# SD-eMMC.net
KiCad netlist of a schematic drawn in Altium Designer
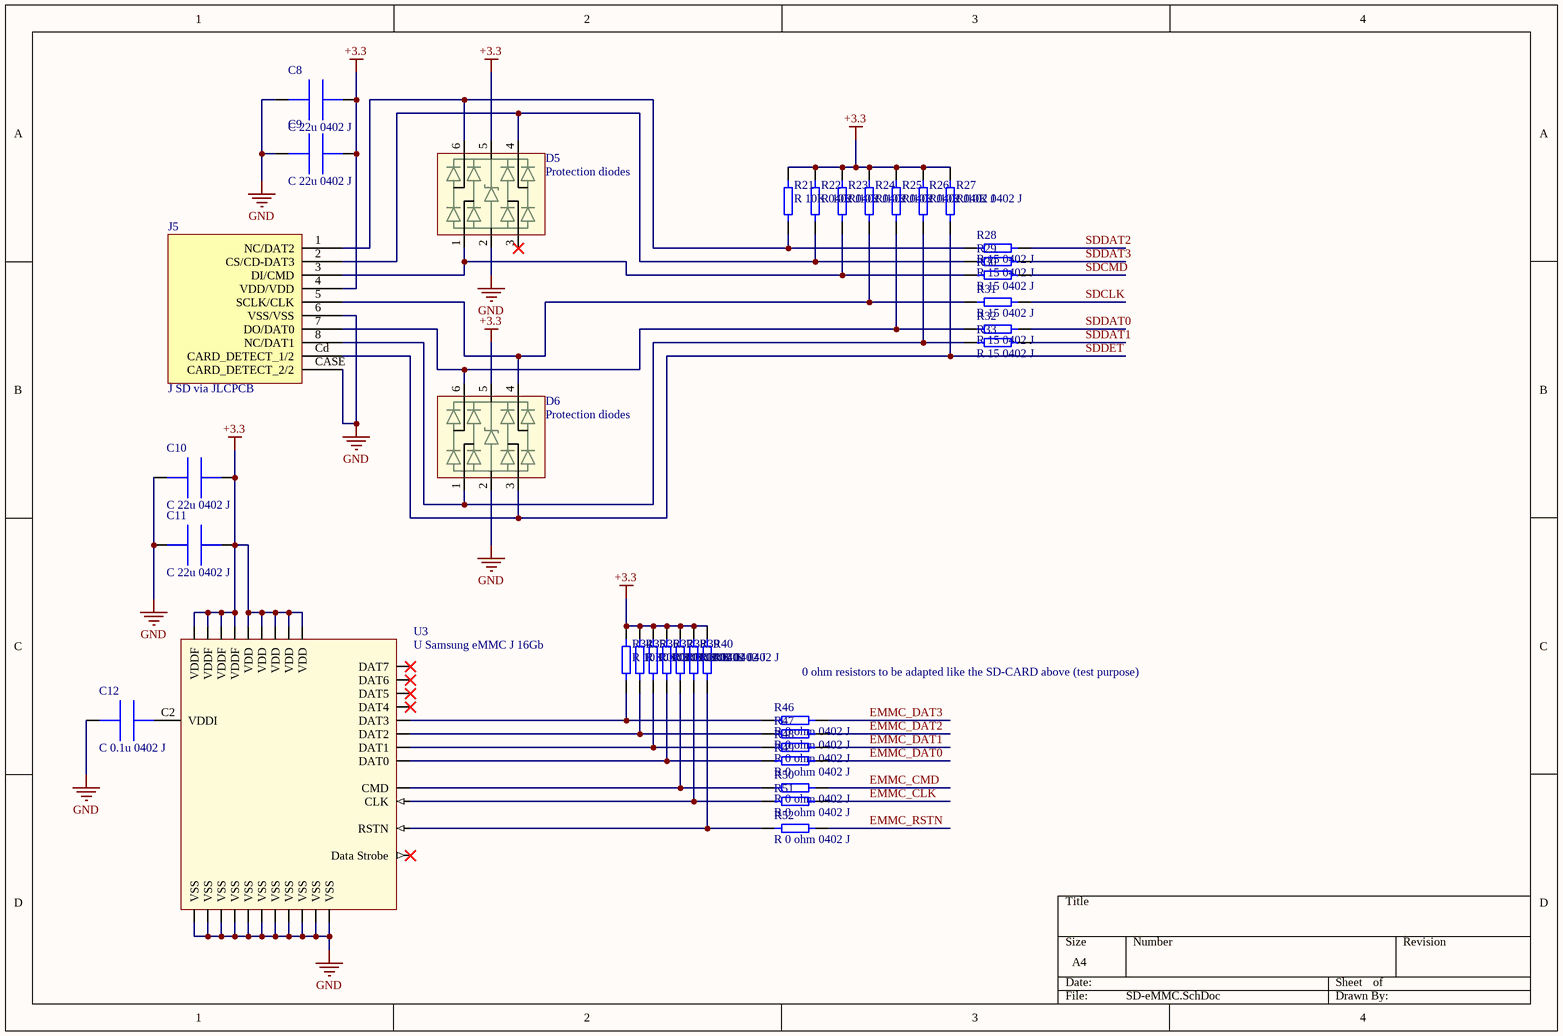
[diagram p0: SD-eMMC.SchDoc]

(export (version "E")
  (design (tool "Eeschema 10.0.6"))
  (components
    (comp (ref "C8")
      (value "C 22u 0402 J")
      (footprint "C0402")
      (description "Multi-Layer Ceramic Capacitor 22uF 2.5VDC X6S 20% 0402 Paper T/R GRM155C80E226ME11D")
      (fields
        (field (name "MANUFACTURER") "Murata")
        (field (name "MANUFACTURER PART NUMBER") "GRM155C80E226ME11D")
      )
      (libsource (lib "Schlib1") (part "C 22u 0402 J"))
    )
    (comp (ref "C9")
      (value "C 22u 0402 J")
      (footprint "C0402")
      (description "Multi-Layer Ceramic Capacitor 22uF 2.5VDC X6S 20% 0402 Paper T/R GRM155C80E226ME11D")
      (fields
        (field (name "MANUFACTURER") "Murata")
        (field (name "MANUFACTURER PART NUMBER") "GRM155C80E226ME11D")
      )
      (libsource (lib "Schlib1") (part "C 22u 0402 J"))
    )
    (comp (ref "C10")
      (value "C 22u 0402 J")
      (footprint "C0402")
      (description "Multi-Layer Ceramic Capacitor 22uF 2.5VDC X6S 20% 0402 Paper T/R GRM155C80E226ME11D")
      (fields
        (field (name "MANUFACTURER") "Murata")
        (field (name "MANUFACTURER PART NUMBER") "GRM155C80E226ME11D")
      )
      (libsource (lib "Schlib1") (part "C 22u 0402 J"))
    )
    (comp (ref "C11")
      (value "C 22u 0402 J")
      (footprint "C0402")
      (description "Multi-Layer Ceramic Capacitor 22uF 2.5VDC X6S 20% 0402 Paper T/R GRM155C80E226ME11D")
      (fields
        (field (name "MANUFACTURER") "Murata")
        (field (name "MANUFACTURER PART NUMBER") "GRM155C80E226ME11D")
      )
      (libsource (lib "Schlib1") (part "C 22u 0402 J"))
    )
    (comp (ref "C12")
      (value "C 0.1u 0402 J")
      (footprint "C0402")
      (description "Cap Ceramic 0.1uF 50V X7R 10% Pad SMD 0402 125C Low ESR Automotive CL05B104KB54PNC")
      (fields
        (field (name "MANUFACTURER") "Samsung")
        (field (name "MANUFACTURER PART NUMBER") "CL05B104KB54PNC")
      )
      (libsource (lib "Schlib1") (part "C 0.1u 0402 J"))
    )
    (comp (ref "D5")
      (value "Protection diodes")
      (footprint "SOT23-SRV05")
      (description "SEMTECH - SRV05-4.TCT - ESD Protection Device, TVS, 17.5 V, SOT-23, 6 Pins, 5 V, 300 W")
      (fields (field (name "MANUFACTURER") "Semtech") (field (name "MANUFACTURER PART NUMBER") "SRV05-4.TCT"))
      (libsource (lib "Schlib1") (part "D SRV05-4.TCT"))
    )
    (comp (ref "D6")
      (value "Protection diodes")
      (footprint "SOT23-SRV05")
      (description "SEMTECH - SRV05-4.TCT - ESD Protection Device, TVS, 17.5 V, SOT-23, 6 Pins, 5 V, 300 W")
      (fields (field (name "MANUFACTURER") "Semtech") (field (name "MANUFACTURER PART NUMBER") "SRV05-4.TCT"))
      (libsource (lib "Schlib1") (part "D SRV05-4.TCT"))
    )
    (comp (ref "J5")
      (value "J SD via JLCPCB")
      (footprint "SOFNG TF-15X15 SD JLCPCB")
      (description "Deck MicroSD card (TF card) Self bomb SMD SD Card Connectors ROHS")
      (fields (field (name "MANUFACTURER") "SOFNG") (field (name "MANUFACTURER PART NUMBER") "TF-15x15"))
      (libsource (lib "Schlib1") (part "J SD via JLCPCB"))
    )
    (comp (ref "R21")
      (value "R 10K 0402 J")
      (footprint "R0402")
      (description "Res Thick Film 0402 10K Ohm 1% 0.063W(1/16W) ±100ppm/C Pad SMD Automotive T/R AC0402FR-0710KL")
      (fields
        (field (name "MANUFACTURER") "Yageo")
        (field (name "MANUFACTURER PART NUMBER") "AC0402FR-0710KL")
      )
      (libsource (lib "Schlib1") (part "R 10K 0402 J"))
    )
    (comp (ref "R22")
      (value "R 10K 0402 J")
      (footprint "R0402")
      (description "Res Thick Film 0402 10K Ohm 1% 0.063W(1/16W) ±100ppm/C Pad SMD Automotive T/R AC0402FR-0710KL")
      (fields
        (field (name "MANUFACTURER") "Yageo")
        (field (name "MANUFACTURER PART NUMBER") "AC0402FR-0710KL")
      )
      (libsource (lib "Schlib1") (part "R 10K 0402 J"))
    )
    (comp (ref "R23")
      (value "R 10K 0402 J")
      (footprint "R0402")
      (description "Res Thick Film 0402 10K Ohm 1% 0.063W(1/16W) ±100ppm/C Pad SMD Automotive T/R AC0402FR-0710KL")
      (fields
        (field (name "MANUFACTURER") "Yageo")
        (field (name "MANUFACTURER PART NUMBER") "AC0402FR-0710KL")
      )
      (libsource (lib "Schlib1") (part "R 10K 0402 J"))
    )
    (comp (ref "R24")
      (value "R 10K 0402 J")
      (footprint "R0402")
      (description "Res Thick Film 0402 10K Ohm 1% 0.063W(1/16W) ±100ppm/C Pad SMD Automotive T/R AC0402FR-0710KL")
      (fields
        (field (name "MANUFACTURER") "Yageo")
        (field (name "MANUFACTURER PART NUMBER") "AC0402FR-0710KL")
      )
      (libsource (lib "Schlib1") (part "R 10K 0402 J"))
    )
    (comp (ref "R25")
      (value "R 10K 0402 J")
      (footprint "R0402")
      (description "Res Thick Film 0402 10K Ohm 1% 0.063W(1/16W) ±100ppm/C Pad SMD Automotive T/R AC0402FR-0710KL")
      (fields
        (field (name "MANUFACTURER") "Yageo")
        (field (name "MANUFACTURER PART NUMBER") "AC0402FR-0710KL")
      )
      (libsource (lib "Schlib1") (part "R 10K 0402 J"))
    )
    (comp (ref "R26")
      (value "R 10K 0402 J")
      (footprint "R0402")
      (description "Res Thick Film 0402 10K Ohm 1% 0.063W(1/16W) ±100ppm/C Pad SMD Automotive T/R AC0402FR-0710KL")
      (fields
        (field (name "MANUFACTURER") "Yageo")
        (field (name "MANUFACTURER PART NUMBER") "AC0402FR-0710KL")
      )
      (libsource (lib "Schlib1") (part "R 10K 0402 J"))
    )
    (comp (ref "R27")
      (value "R 10K 0402 J")
      (footprint "R0402")
      (description "Res Thick Film 0402 10K Ohm 1% 0.063W(1/16W) ±100ppm/C Pad SMD Automotive T/R AC0402FR-0710KL")
      (fields
        (field (name "MANUFACTURER") "Yageo")
        (field (name "MANUFACTURER PART NUMBER") "AC0402FR-0710KL")
      )
      (libsource (lib "Schlib1") (part "R 10K 0402 J"))
    )
    (comp (ref "R28")
      (value "R 15 0402 J")
      (footprint "R0402")
      (description "Res Thick Film 0402 15 Ohm 5% 1/10W ±200ppm/°C Molded SMD Punched Carrier T/R ERJ-2GEJ150X")
      (fields
        (field (name "MANUFACTURER") "Panasonic")
        (field (name "MANUFACTURER PART NUMBER") "ERJ-2GEJ150X")
      )
      (libsource (lib "Schlib1") (part "R 15 0402 J"))
    )
    (comp (ref "R29")
      (value "R 15 0402 J")
      (footprint "R0402")
      (description "Res Thick Film 0402 15 Ohm 5% 1/10W ±200ppm/°C Molded SMD Punched Carrier T/R ERJ-2GEJ150X")
      (fields
        (field (name "MANUFACTURER") "Panasonic")
        (field (name "MANUFACTURER PART NUMBER") "ERJ-2GEJ150X")
      )
      (libsource (lib "Schlib1") (part "R 15 0402 J"))
    )
    (comp (ref "R30")
      (value "R 15 0402 J")
      (footprint "R0402")
      (description "Res Thick Film 0402 15 Ohm 5% 1/10W ±200ppm/°C Molded SMD Punched Carrier T/R ERJ-2GEJ150X")
      (fields
        (field (name "MANUFACTURER") "Panasonic")
        (field (name "MANUFACTURER PART NUMBER") "ERJ-2GEJ150X")
      )
      (libsource (lib "Schlib1") (part "R 15 0402 J"))
    )
    (comp (ref "R31")
      (value "R 15 0402 J")
      (footprint "R0402")
      (description "Res Thick Film 0402 15 Ohm 5% 1/10W ±200ppm/°C Molded SMD Punched Carrier T/R ERJ-2GEJ150X")
      (fields
        (field (name "MANUFACTURER") "Panasonic")
        (field (name "MANUFACTURER PART NUMBER") "ERJ-2GEJ150X")
      )
      (libsource (lib "Schlib1") (part "R 15 0402 J"))
    )
    (comp (ref "R32")
      (value "R 15 0402 J")
      (footprint "R0402")
      (description "Res Thick Film 0402 15 Ohm 5% 1/10W ±200ppm/°C Molded SMD Punched Carrier T/R ERJ-2GEJ150X")
      (fields
        (field (name "MANUFACTURER") "Panasonic")
        (field (name "MANUFACTURER PART NUMBER") "ERJ-2GEJ150X")
      )
      (libsource (lib "Schlib1") (part "R 15 0402 J"))
    )
    (comp (ref "R33")
      (value "R 15 0402 J")
      (footprint "R0402")
      (description "Res Thick Film 0402 15 Ohm 5% 1/10W ±200ppm/°C Molded SMD Punched Carrier T/R ERJ-2GEJ150X")
      (fields
        (field (name "MANUFACTURER") "Panasonic")
        (field (name "MANUFACTURER PART NUMBER") "ERJ-2GEJ150X")
      )
      (libsource (lib "Schlib1") (part "R 15 0402 J"))
    )
    (comp (ref "R34")
      (value "R 10K 0402 J")
      (footprint "R0402")
      (description "Res Thick Film 0402 10K Ohm 1% 0.063W(1/16W) ±100ppm/C Pad SMD Automotive T/R AC0402FR-0710KL")
      (fields
        (field (name "MANUFACTURER") "Yageo")
        (field (name "MANUFACTURER PART NUMBER") "AC0402FR-0710KL")
      )
      (libsource (lib "Schlib1") (part "R 10K 0402 J"))
    )
    (comp (ref "R35")
      (value "R 10K 0402 J")
      (footprint "R0402")
      (description "Res Thick Film 0402 10K Ohm 1% 0.063W(1/16W) ±100ppm/C Pad SMD Automotive T/R AC0402FR-0710KL")
      (fields
        (field (name "MANUFACTURER") "Yageo")
        (field (name "MANUFACTURER PART NUMBER") "AC0402FR-0710KL")
      )
      (libsource (lib "Schlib1") (part "R 10K 0402 J"))
    )
    (comp (ref "R36")
      (value "R 10K 0402 J")
      (footprint "R0402")
      (description "Res Thick Film 0402 10K Ohm 1% 0.063W(1/16W) ±100ppm/C Pad SMD Automotive T/R AC0402FR-0710KL")
      (fields
        (field (name "MANUFACTURER") "Yageo")
        (field (name "MANUFACTURER PART NUMBER") "AC0402FR-0710KL")
      )
      (libsource (lib "Schlib1") (part "R 10K 0402 J"))
    )
    (comp (ref "R37")
      (value "R 10K 0402 J")
      (footprint "R0402")
      (description "Res Thick Film 0402 10K Ohm 1% 0.063W(1/16W) ±100ppm/C Pad SMD Automotive T/R AC0402FR-0710KL")
      (fields
        (field (name "MANUFACTURER") "Yageo")
        (field (name "MANUFACTURER PART NUMBER") "AC0402FR-0710KL")
      )
      (libsource (lib "Schlib1") (part "R 10K 0402 J"))
    )
    (comp (ref "R38")
      (value "R 10K 0402 J")
      (footprint "R0402")
      (description "Res Thick Film 0402 10K Ohm 1% 0.063W(1/16W) ±100ppm/C Pad SMD Automotive T/R AC0402FR-0710KL")
      (fields
        (field (name "MANUFACTURER") "Yageo")
        (field (name "MANUFACTURER PART NUMBER") "AC0402FR-0710KL")
      )
      (libsource (lib "Schlib1") (part "R 10K 0402 J"))
    )
    (comp (ref "R39")
      (value "R 10K 0402 J")
      (footprint "R0402")
      (description "Res Thick Film 0402 10K Ohm 1% 0.063W(1/16W) ±100ppm/C Pad SMD Automotive T/R AC0402FR-0710KL")
      (fields
        (field (name "MANUFACTURER") "Yageo")
        (field (name "MANUFACTURER PART NUMBER") "AC0402FR-0710KL")
      )
      (libsource (lib "Schlib1") (part "R 10K 0402 J"))
    )
    (comp (ref "R40")
      (value "R 10K 0402 J")
      (footprint "R0402")
      (description "Res Thick Film 0402 10K Ohm 1% 0.063W(1/16W) ±100ppm/C Pad SMD Automotive T/R AC0402FR-0710KL")
      (fields
        (field (name "MANUFACTURER") "Yageo")
        (field (name "MANUFACTURER PART NUMBER") "AC0402FR-0710KL")
      )
      (libsource (lib "Schlib1") (part "R 10K 0402 J"))
    )
    (comp (ref "R46")
      (value "R 0 ohm 0402 J")
      (footprint "R0402")
      (description "RC Series 0402 0.063 W 0 Ohm Jumper Surface Mount Thick Film Chip Resistor RC0402FR-070RL")
      (fields
        (field (name "MANUFACTURER") "Yageo")
        (field (name "MANUFACTURER PART NUMBER") "RC0402FR-070RL")
      )
      (libsource (lib "Schlib1") (part "R 0 ohm 0402 J"))
    )
    (comp (ref "R47")
      (value "R 0 ohm 0402 J")
      (footprint "R0402")
      (description "RC Series 0402 0.063 W 0 Ohm Jumper Surface Mount Thick Film Chip Resistor RC0402FR-070RL")
      (fields
        (field (name "MANUFACTURER") "Yageo")
        (field (name "MANUFACTURER PART NUMBER") "RC0402FR-070RL")
      )
      (libsource (lib "Schlib1") (part "R 0 ohm 0402 J"))
    )
    (comp (ref "R48")
      (value "R 0 ohm 0402 J")
      (footprint "R0402")
      (description "RC Series 0402 0.063 W 0 Ohm Jumper Surface Mount Thick Film Chip Resistor RC0402FR-070RL")
      (fields
        (field (name "MANUFACTURER") "Yageo")
        (field (name "MANUFACTURER PART NUMBER") "RC0402FR-070RL")
      )
      (libsource (lib "Schlib1") (part "R 0 ohm 0402 J"))
    )
    (comp (ref "R49")
      (value "R 0 ohm 0402 J")
      (footprint "R0402")
      (description "RC Series 0402 0.063 W 0 Ohm Jumper Surface Mount Thick Film Chip Resistor RC0402FR-070RL")
      (fields
        (field (name "MANUFACTURER") "Yageo")
        (field (name "MANUFACTURER PART NUMBER") "RC0402FR-070RL")
      )
      (libsource (lib "Schlib1") (part "R 0 ohm 0402 J"))
    )
    (comp (ref "R50")
      (value "R 0 ohm 0402 J")
      (footprint "R0402")
      (description "RC Series 0402 0.063 W 0 Ohm Jumper Surface Mount Thick Film Chip Resistor RC0402FR-070RL")
      (fields
        (field (name "MANUFACTURER") "Yageo")
        (field (name "MANUFACTURER PART NUMBER") "RC0402FR-070RL")
      )
      (libsource (lib "Schlib1") (part "R 0 ohm 0402 J"))
    )
    (comp (ref "R51")
      (value "R 0 ohm 0402 J")
      (footprint "R0402")
      (description "RC Series 0402 0.063 W 0 Ohm Jumper Surface Mount Thick Film Chip Resistor RC0402FR-070RL")
      (fields
        (field (name "MANUFACTURER") "Yageo")
        (field (name "MANUFACTURER PART NUMBER") "RC0402FR-070RL")
      )
      (libsource (lib "Schlib1") (part "R 0 ohm 0402 J"))
    )
    (comp (ref "R52")
      (value "R 0 ohm 0402 J")
      (footprint "R0402")
      (description "RC Series 0402 0.063 W 0 Ohm Jumper Surface Mount Thick Film Chip Resistor RC0402FR-070RL")
      (fields
        (field (name "MANUFACTURER") "Yageo")
        (field (name "MANUFACTURER PART NUMBER") "RC0402FR-070RL")
      )
      (libsource (lib "Schlib1") (part "R 0 ohm 0402 J"))
    )
    (comp (ref "U3")
      (value "U Samsung eMMC J 16Gb")
      (footprint "BGA153C50P14X14_1150X1300X92")
      (description "KLMAG1JETD-B041 16Gbit -25℃~+85℃ 2.7V~3.6V eMMC 5.1 FBGA-153 eMMC ROHS")
      (fields
        (field (name "MANUFACTURER") "Samsung")
        (field (name "MANUFACTURER PART NUMBER") "KLMAG1JETD-B041")
      )
      (libsource (lib "Schlib1") (part "U Samsung eMMC J 16Gb"))
    )
  )
  (nets
    (net (code "1") (name "+3.3") (class "Default")
      (node (ref "C10") (pin "2") (pinfunction "2_2") (pintype "passive"))
      (node (ref "C11") (pin "2") (pinfunction "2_2") (pintype "passive"))
      (node (ref "C8") (pin "2") (pinfunction "2_2") (pintype "passive"))
      (node (ref "C9") (pin "2") (pinfunction "2_2") (pintype "passive"))
      (node (ref "D5") (pin "5") (pinfunction "5_5") (pintype "passive"))
      (node (ref "D6") (pin "5") (pinfunction "5_5") (pintype "passive"))
      (node (ref "J5") (pin "4") (pinfunction "VDD/VDD_4") (pintype "passive"))
      (node (ref "R21") (pin "2") (pinfunction "2_2") (pintype "passive"))
      (node (ref "R22") (pin "2") (pinfunction "2_2") (pintype "passive"))
      (node (ref "R23") (pin "2") (pinfunction "2_2") (pintype "passive"))
      (node (ref "R24") (pin "2") (pinfunction "2_2") (pintype "passive"))
      (node (ref "R25") (pin "2") (pinfunction "2_2") (pintype "passive"))
      (node (ref "R26") (pin "2") (pinfunction "2_2") (pintype "passive"))
      (node (ref "R27") (pin "2") (pinfunction "2_2") (pintype "passive"))
      (node (ref "R34") (pin "2") (pinfunction "2_2") (pintype "passive"))
      (node (ref "R35") (pin "2") (pinfunction "2_2") (pintype "passive"))
      (node (ref "R36") (pin "2") (pinfunction "2_2") (pintype "passive"))
      (node (ref "R37") (pin "2") (pinfunction "2_2") (pintype "passive"))
      (node (ref "R38") (pin "1") (pinfunction "1_1") (pintype "passive"))
      (node (ref "R39") (pin "2") (pinfunction "2_2") (pintype "passive"))
      (node (ref "R40") (pin "1") (pinfunction "1_1") (pintype "passive"))
      (node (ref "U3") (pin "C6") (pinfunction "VDD_C6") (pintype "power_in"))
      (node (ref "U3") (pin "E6") (pinfunction "VDDF_E6") (pintype "power_in"))
      (node (ref "U3") (pin "F5") (pinfunction "VDDF_F5") (pintype "power_in"))
      (node (ref "U3") (pin "J10") (pinfunction "VDDF_J10") (pintype "power_in"))
      (node (ref "U3") (pin "K9") (pinfunction "VDDF_K9") (pintype "power_in"))
      (node (ref "U3") (pin "M4") (pinfunction "VDD_M4") (pintype "power_in"))
      (node (ref "U3") (pin "N4") (pinfunction "VDD_N4") (pintype "power_in"))
      (node (ref "U3") (pin "P3") (pinfunction "VDD_P3") (pintype "power_in"))
      (node (ref "U3") (pin "P5") (pinfunction "VDD_P5") (pintype "power_in"))
    )
    (net (code "2") (name "/EMMC_CLK") (class "Default")
      (node (ref "R51") (pin "2") (pinfunction "2_2") (pintype "passive"))
    )
    (net (code "3") (name "/EMMC_CMD") (class "Default")
      (node (ref "R50") (pin "2") (pinfunction "2_2") (pintype "passive"))
    )
    (net (code "4") (name "/EMMC_DAT0") (class "Default")
      (node (ref "R49") (pin "2") (pinfunction "2_2") (pintype "passive"))
    )
    (net (code "5") (name "/EMMC_DAT1") (class "Default")
      (node (ref "R48") (pin "2") (pinfunction "2_2") (pintype "passive"))
    )
    (net (code "6") (name "/EMMC_DAT2") (class "Default")
      (node (ref "R47") (pin "2") (pinfunction "2_2") (pintype "passive"))
    )
    (net (code "7") (name "/EMMC_DAT3") (class "Default")
      (node (ref "R46") (pin "2") (pinfunction "2_2") (pintype "passive"))
    )
    (net (code "8") (name "/EMMC_RSTN") (class "Default")
      (node (ref "R52") (pin "2") (pinfunction "2_2") (pintype "passive"))
    )
    (net (code "9") (name "/SDCLK") (class "Default")
      (node (ref "R31") (pin "2") (pinfunction "2_2") (pintype "passive"))
    )
    (net (code "10") (name "/SDCMD") (class "Default")
      (node (ref "R30") (pin "2") (pinfunction "2_2") (pintype "passive"))
    )
    (net (code "11") (name "/SDDAT0") (class "Default")
      (node (ref "R32") (pin "2") (pinfunction "2_2") (pintype "passive"))
    )
    (net (code "12") (name "/SDDAT1") (class "Default")
      (node (ref "R33") (pin "2") (pinfunction "2_2") (pintype "passive"))
    )
    (net (code "13") (name "/SDDAT2") (class "Default")
      (node (ref "R28") (pin "2") (pinfunction "2_2") (pintype "passive"))
    )
    (net (code "14") (name "/SDDAT3") (class "Default")
      (node (ref "R29") (pin "2") (pinfunction "2_2") (pintype "passive"))
    )
    (net (code "15") (name "/SDDET") (class "Default")
      (node (ref "D6") (pin "3") (pinfunction "3_3") (pintype "passive"))
      (node (ref "J5") (pin "Cd") (pinfunction "CARD_DETECT_1/2_Cd") (pintype "passive"))
      (node (ref "R27") (pin "1") (pinfunction "1_1") (pintype "passive"))
    )
    (net (code "16") (name "GND") (class "Default")
      (node (ref "C10") (pin "1") (pinfunction "1_1") (pintype "passive"))
      (node (ref "C11") (pin "1") (pinfunction "1_1") (pintype "passive"))
      (node (ref "C12") (pin "1") (pinfunction "1_1") (pintype "passive"))
      (node (ref "C8") (pin "1") (pinfunction "1_1") (pintype "passive"))
      (node (ref "C9") (pin "1") (pinfunction "1_1") (pintype "passive"))
      (node (ref "D5") (pin "2") (pinfunction "2_2") (pintype "passive"))
      (node (ref "D6") (pin "2") (pinfunction "2_2") (pintype "passive"))
      (node (ref "J5") (pin "6") (pinfunction "VSS/VSS_6") (pintype "passive"))
      (node (ref "J5") (pin "CASE") (pinfunction "CARD_DETECT_2/2_CASE") (pintype "passive"))
      (node (ref "U3") (pin "A6") (pinfunction "VSS_A6") (pintype "power_in"))
      (node (ref "U3") (pin "C4") (pinfunction "VSS_C4") (pintype "power_in"))
      (node (ref "U3") (pin "E7") (pinfunction "VSS_E7") (pintype "power_in"))
      (node (ref "U3") (pin "G5") (pinfunction "VSS_G5") (pintype "power_in"))
      (node (ref "U3") (pin "H10") (pinfunction "VSS_H10") (pintype "power_in"))
      (node (ref "U3") (pin "J5") (pinfunction "VSS_J5") (pintype "power_in"))
      (node (ref "U3") (pin "K8") (pinfunction "VSS_K8") (pintype "power_in"))
      (node (ref "U3") (pin "N2") (pinfunction "VSS_N2") (pintype "power_in"))
      (node (ref "U3") (pin "N5") (pinfunction "VSS_N5") (pintype "power_in"))
      (node (ref "U3") (pin "P4") (pinfunction "VSS_P4") (pintype "power_in"))
      (node (ref "U3") (pin "P6") (pinfunction "VSS_P6") (pintype "power_in"))
    )
    (net (code "17") (name "Net-(J5-CS{slash}CD-DAT3)") (class "Default")
      (node (ref "D5") (pin "4") (pinfunction "4_4") (pintype "passive"))
      (node (ref "J5") (pin "2") (pinfunction "CS/CD-DAT3_2") (pintype "passive"))
      (node (ref "R22") (pin "1") (pinfunction "1_1") (pintype "passive"))
      (node (ref "R29") (pin "1") (pinfunction "1_1") (pintype "passive"))
    )
    (net (code "18") (name "Net-(J5-DI{slash}CMD)") (class "Default")
      (node (ref "D5") (pin "1") (pinfunction "1_1") (pintype "passive"))
      (node (ref "J5") (pin "3") (pinfunction "DI/CMD_3") (pintype "passive"))
      (node (ref "R23") (pin "1") (pinfunction "1_1") (pintype "passive"))
      (node (ref "R30") (pin "1") (pinfunction "1_1") (pintype "passive"))
    )
    (net (code "19") (name "Net-(J5-DO{slash}DAT0)") (class "Default")
      (node (ref "D6") (pin "6") (pinfunction "6_6") (pintype "passive"))
      (node (ref "J5") (pin "7") (pinfunction "DO/DAT0_7") (pintype "passive"))
      (node (ref "R25") (pin "1") (pinfunction "1_1") (pintype "passive"))
      (node (ref "R32") (pin "1") (pinfunction "1_1") (pintype "passive"))
    )
    (net (code "20") (name "Net-(J5-NC{slash}DAT1)") (class "Default")
      (node (ref "D6") (pin "1") (pinfunction "1_1") (pintype "passive"))
      (node (ref "J5") (pin "8") (pinfunction "NC/DAT1_8") (pintype "passive"))
      (node (ref "R26") (pin "1") (pinfunction "1_1") (pintype "passive"))
      (node (ref "R33") (pin "1") (pinfunction "1_1") (pintype "passive"))
    )
    (net (code "21") (name "Net-(J5-NC{slash}DAT2)") (class "Default")
      (node (ref "D5") (pin "6") (pinfunction "6_6") (pintype "passive"))
      (node (ref "J5") (pin "1") (pinfunction "NC/DAT2_1") (pintype "passive"))
      (node (ref "R21") (pin "1") (pinfunction "1_1") (pintype "passive"))
      (node (ref "R28") (pin "1") (pinfunction "1_1") (pintype "passive"))
    )
    (net (code "22") (name "Net-(J5-SCLK{slash}CLK)") (class "Default")
      (node (ref "D6") (pin "4") (pinfunction "4_4") (pintype "passive"))
      (node (ref "J5") (pin "5") (pinfunction "SCLK/CLK_5") (pintype "passive"))
      (node (ref "R24") (pin "1") (pinfunction "1_1") (pintype "passive"))
      (node (ref "R31") (pin "1") (pinfunction "1_1") (pintype "passive"))
    )
    (net (code "23") (name "Net-(U3-CLK)") (class "Default")
      (node (ref "R39") (pin "1") (pinfunction "1_1") (pintype "passive"))
      (node (ref "R51") (pin "1") (pinfunction "1_1") (pintype "passive"))
      (node (ref "U3") (pin "M6") (pinfunction "CLK_M6") (pintype "input"))
    )
    (net (code "24") (name "Net-(U3-CMD)") (class "Default")
      (node (ref "R38") (pin "2") (pinfunction "2_2") (pintype "passive"))
      (node (ref "R50") (pin "1") (pinfunction "1_1") (pintype "passive"))
      (node (ref "U3") (pin "M5") (pinfunction "CMD_M5") (pintype "bidirectional"))
    )
    (net (code "25") (name "Net-(U3-DAT0)") (class "Default")
      (node (ref "R37") (pin "1") (pinfunction "1_1") (pintype "passive"))
      (node (ref "R49") (pin "1") (pinfunction "1_1") (pintype "passive"))
      (node (ref "U3") (pin "A3") (pinfunction "DAT0_A3") (pintype "bidirectional"))
    )
    (net (code "26") (name "Net-(U3-DAT1)") (class "Default")
      (node (ref "R36") (pin "1") (pinfunction "1_1") (pintype "passive"))
      (node (ref "R48") (pin "1") (pinfunction "1_1") (pintype "passive"))
      (node (ref "U3") (pin "A4") (pinfunction "DAT1_A4") (pintype "bidirectional"))
    )
    (net (code "27") (name "Net-(U3-DAT2)") (class "Default")
      (node (ref "R35") (pin "1") (pinfunction "1_1") (pintype "passive"))
      (node (ref "R47") (pin "1") (pinfunction "1_1") (pintype "passive"))
      (node (ref "U3") (pin "A5") (pinfunction "DAT2_A5") (pintype "bidirectional"))
    )
    (net (code "28") (name "Net-(U3-DAT3)") (class "Default")
      (node (ref "R34") (pin "1") (pinfunction "1_1") (pintype "passive"))
      (node (ref "R46") (pin "1") (pinfunction "1_1") (pintype "passive"))
      (node (ref "U3") (pin "B2") (pinfunction "DAT3_B2") (pintype "bidirectional"))
    )
    (net (code "29") (name "Net-(U3-RSTN)") (class "Default")
      (node (ref "R40") (pin "2") (pinfunction "2_2") (pintype "passive"))
      (node (ref "R52") (pin "1") (pinfunction "1_1") (pintype "passive"))
      (node (ref "U3") (pin "K5") (pinfunction "RSTN_K5") (pintype "input"))
    )
    (net (code "30") (name "Net-(U3-VDDI)") (class "Default")
      (node (ref "C12") (pin "2") (pinfunction "2_2") (pintype "passive"))
      (node (ref "U3") (pin "C2") (pinfunction "VDDI_C2") (pintype "passive"))
    )
    (net (code "31") (name "unconnected-(D5-Pad3)") (class "Default")
      (node (ref "D5") (pin "3") (pinfunction "3_3") (pintype "passive+no_connect"))
    )
    (net (code "32") (name "unconnected-(U3-DAT4-PadB3)") (class "Default")
      (node (ref "U3") (pin "B3") (pinfunction "DAT4_B3") (pintype "bidirectional+no_connect"))
    )
    (net (code "33") (name "unconnected-(U3-DAT5-PadB4)") (class "Default")
      (node (ref "U3") (pin "B4") (pinfunction "DAT5_B4") (pintype "bidirectional+no_connect"))
    )
    (net (code "34") (name "unconnected-(U3-DAT6-PadB5)") (class "Default")
      (node (ref "U3") (pin "B5") (pinfunction "DAT6_B5") (pintype "bidirectional+no_connect"))
    )
    (net (code "35") (name "unconnected-(U3-DAT7-PadB6)") (class "Default")
      (node (ref "U3") (pin "B6") (pinfunction "DAT7_B6") (pintype "bidirectional+no_connect"))
    )
    (net (code "36") (name "unconnected-(U3-Data_Strobe-PadH5)") (class "Default")
      (node (ref "U3") (pin "H5") (pinfunction "Data_Strobe_H5") (pintype "output+no_connect"))
    )
  )
)
